# Sheet2.net
KiCad netlist of a schematic drawn in Altium Designer
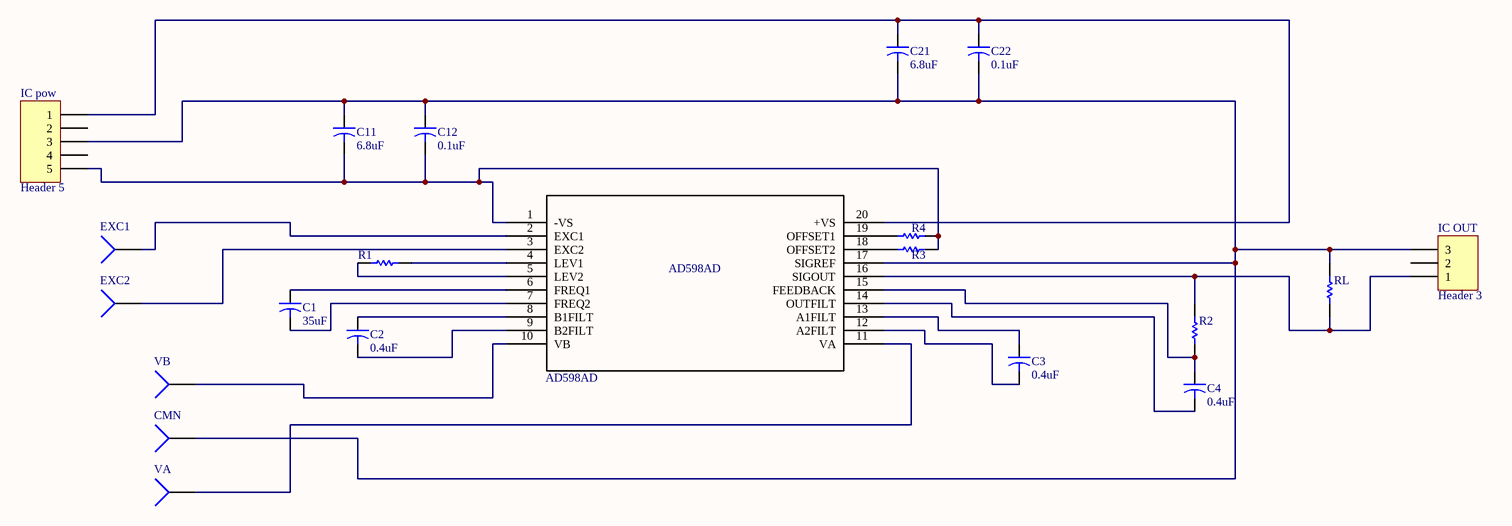
[diagram p0: Sheet2.SchDoc]

(export (version "E")
  (design (tool "Eeschema 10.0.6"))
  (components
    (comp (ref "AD598AD")
      (value "AD598AD")
      (footprint "D_20")
      (description "Imported")
      (libsource (lib "2014-03-15_12-02-51") (part "AD598AD"))
    )
    (comp (ref "C1")
      (value "35uF")
      (footprint "CAPR5-4X5")
      (description "Capacitor")
      (fields (field (name "Comment") "Cap2") (field (name "PUBLISHER") "Altium Limited"))
      (libsource (lib "Miscellaneous Devices") (part "Cap2"))
    )
    (comp (ref "C2")
      (value "0.4uF")
      (footprint "CAPR5-4X5")
      (description "Capacitor")
      (fields (field (name "Comment") "Cap2") (field (name "PUBLISHER") "Altium Limited"))
      (libsource (lib "Miscellaneous Devices") (part "Cap2"))
    )
    (comp (ref "C3")
      (value "0.4uF")
      (footprint "CAPR5-4X5")
      (description "Capacitor")
      (fields (field (name "Comment") "Cap2") (field (name "PUBLISHER") "Altium Limited"))
      (libsource (lib "Miscellaneous Devices") (part "Cap2"))
    )
    (comp (ref "C4")
      (value "0.4uF")
      (footprint "CAPR5-4X5")
      (description "Capacitor")
      (fields (field (name "Comment") "Cap2") (field (name "PUBLISHER") "Altium Limited"))
      (libsource (lib "Miscellaneous Devices") (part "Cap2"))
    )
    (comp (ref "C11")
      (value "6.8uF")
      (footprint "CAPR5-4X5")
      (description "Capacitor")
      (fields (field (name "Comment") "Cap2") (field (name "PUBLISHER") "Altium Limited"))
      (libsource (lib "Miscellaneous Devices") (part "Cap2"))
    )
    (comp (ref "C12")
      (value "0.1uF")
      (footprint "CAPR5-4X5")
      (description "Capacitor")
      (fields (field (name "Comment") "Cap2") (field (name "PUBLISHER") "Altium Limited"))
      (libsource (lib "Miscellaneous Devices") (part "Cap2"))
    )
    (comp (ref "C21")
      (value "6.8uF")
      (footprint "CAPR5-4X5")
      (description "Capacitor")
      (fields (field (name "Comment") "Cap2") (field (name "PUBLISHER") "Altium Limited"))
      (libsource (lib "Miscellaneous Devices") (part "Cap2"))
    )
    (comp (ref "C22")
      (value "0.1uF")
      (footprint "CAPR5-4X5")
      (description "Capacitor")
      (fields (field (name "Comment") "Cap2") (field (name "PUBLISHER") "Altium Limited"))
      (libsource (lib "Miscellaneous Devices") (part "Cap2"))
    )
    (comp (ref "CMN")
      (value "Socket")
      (footprint "PIN1")
      (fields (field (name "PUBLISHER") "Altium Limited"))
      (libsource (lib "Miscellaneous Connectors") (part "Socket"))
    )
    (comp (ref "EXC1")
      (value "Socket")
      (footprint "PIN1")
      (fields (field (name "PUBLISHER") "Altium Limited"))
      (libsource (lib "Miscellaneous Connectors") (part "Socket"))
    )
    (comp (ref "EXC2")
      (value "Socket")
      (footprint "PIN1")
      (fields (field (name "PUBLISHER") "Altium Limited"))
      (libsource (lib "Miscellaneous Connectors") (part "Socket"))
    )
    (comp (ref "IC OUT")
      (value "Header 3")
      (footprint "HDR1X3")
      (description "Header, 3-Pin")
      (fields (field (name "PUBLISHER") "Altium Limited"))
      (libsource (lib "Miscellaneous Connectors") (part "Header 3"))
    )
    (comp (ref "IC pow")
      (value "Header 5")
      (footprint "HDR1X5")
      (description "Header, 5-Pin")
      (fields (field (name "PUBLISHER") "Altium Limited"))
      (libsource (lib "Miscellaneous Connectors") (part "Header 5"))
    )
    (comp (ref "R1")
      (value "R1")
      (footprint "AXIAL-0.3")
      (description "Resistor")
      (fields (field (name "PUBLISHER") "Altium Limited"))
      (libsource (lib "Miscellaneous Devices") (part "Res1"))
    )
    (comp (ref "R2")
      (value "Res1")
      (footprint "AXIAL-0.3")
      (description "Resistor")
      (fields (field (name "PUBLISHER") "Altium Limited"))
      (libsource (lib "Miscellaneous Devices") (part "Res1"))
    )
    (comp (ref "R3")
      (value "Res1")
      (footprint "AXIAL-0.3")
      (description "Resistor")
      (fields (field (name "PUBLISHER") "Altium Limited"))
      (libsource (lib "Miscellaneous Devices") (part "Res1"))
    )
    (comp (ref "R4")
      (value "Res1")
      (footprint "AXIAL-0.3")
      (description "Resistor")
      (fields (field (name "PUBLISHER") "Altium Limited"))
      (libsource (lib "Miscellaneous Devices") (part "Res1"))
    )
    (comp (ref "RL")
      (value "Res1")
      (footprint "AXIAL-0.3")
      (description "Resistor")
      (fields (field (name "PUBLISHER") "Altium Limited"))
      (libsource (lib "Miscellaneous Devices") (part "Res1"))
    )
    (comp (ref "VA")
      (value "Socket")
      (footprint "PIN1")
      (fields (field (name "PUBLISHER") "Altium Limited"))
      (libsource (lib "Miscellaneous Connectors") (part "Socket"))
    )
    (comp (ref "VB")
      (value "Socket")
      (footprint "PIN1")
      (fields (field (name "PUBLISHER") "Altium Limited"))
      (libsource (lib "Miscellaneous Connectors") (part "Socket"))
    )
  )
  (nets
    (net (code "1") (name "Net-(AD598AD-+VS)") (class "Default")
      (node (ref "AD598AD") (pin "20") (pinfunction "+VS_20") (pintype "passive"))
      (node (ref "C21") (pin "1") (pinfunction "1_1") (pintype "passive"))
      (node (ref "C22") (pin "1") (pinfunction "1_1") (pintype "passive"))
      (node (ref "IC pow") (pin "1") (pinfunction "1_1") (pintype "passive"))
    )
    (net (code "2") (name "Net-(AD598AD--VS)") (class "Default")
      (node (ref "AD598AD") (pin "1") (pinfunction "-VS_1") (pintype "passive"))
      (node (ref "C11") (pin "2") (pinfunction "2_2") (pintype "passive"))
      (node (ref "C12") (pin "2") (pinfunction "2_2") (pintype "passive"))
      (node (ref "IC pow") (pin "5") (pinfunction "5_5") (pintype "passive"))
      (node (ref "R3") (pin "2") (pinfunction "2_2") (pintype "passive"))
      (node (ref "R4") (pin "2") (pinfunction "2_2") (pintype "passive"))
    )
    (net (code "3") (name "Net-(AD598AD-A1FILT)") (class "Default")
      (node (ref "AD598AD") (pin "13") (pinfunction "A1FILT_13") (pintype "passive"))
      (node (ref "C3") (pin "1") (pinfunction "1_1") (pintype "passive"))
    )
    (net (code "4") (name "Net-(AD598AD-A2FILT)") (class "Default")
      (node (ref "AD598AD") (pin "12") (pinfunction "A2FILT_12") (pintype "passive"))
      (node (ref "C3") (pin "2") (pinfunction "2_2") (pintype "passive"))
    )
    (net (code "5") (name "Net-(AD598AD-B1FILT)") (class "Default")
      (node (ref "AD598AD") (pin "8") (pinfunction "B1FILT_8") (pintype "passive"))
      (node (ref "C2") (pin "1") (pinfunction "1_1") (pintype "passive"))
    )
    (net (code "6") (name "Net-(AD598AD-B2FILT)") (class "Default")
      (node (ref "AD598AD") (pin "9") (pinfunction "B2FILT_9") (pintype "passive"))
      (node (ref "C2") (pin "2") (pinfunction "2_2") (pintype "passive"))
    )
    (net (code "7") (name "Net-(AD598AD-EXC1)") (class "Default")
      (node (ref "AD598AD") (pin "2") (pinfunction "EXC1_2") (pintype "passive"))
      (node (ref "EXC1") (pin "1") (pinfunction "1_1") (pintype "passive"))
    )
    (net (code "8") (name "Net-(AD598AD-EXC2)") (class "Default")
      (node (ref "AD598AD") (pin "3") (pinfunction "EXC2_3") (pintype "passive"))
      (node (ref "EXC2") (pin "1") (pinfunction "1_1") (pintype "passive"))
    )
    (net (code "9") (name "Net-(AD598AD-FEEDBACK)") (class "Default")
      (node (ref "AD598AD") (pin "15") (pinfunction "FEEDBACK_15") (pintype "passive"))
      (node (ref "C4") (pin "1") (pinfunction "1_1") (pintype "passive"))
      (node (ref "R2") (pin "1") (pinfunction "1_1") (pintype "passive"))
    )
    (net (code "10") (name "Net-(AD598AD-FREQ1)") (class "Default")
      (node (ref "AD598AD") (pin "6") (pinfunction "FREQ1_6") (pintype "passive"))
      (node (ref "C1") (pin "1") (pinfunction "1_1") (pintype "passive"))
    )
    (net (code "11") (name "Net-(AD598AD-FREQ2)") (class "Default")
      (node (ref "AD598AD") (pin "7") (pinfunction "FREQ2_7") (pintype "passive"))
      (node (ref "C1") (pin "2") (pinfunction "2_2") (pintype "passive"))
    )
    (net (code "12") (name "Net-(AD598AD-LEV1)") (class "Default")
      (node (ref "AD598AD") (pin "4") (pinfunction "LEV1_4") (pintype "passive"))
      (node (ref "R1") (pin "1") (pinfunction "1_1") (pintype "passive"))
    )
    (net (code "13") (name "Net-(AD598AD-LEV2)") (class "Default")
      (node (ref "AD598AD") (pin "5") (pinfunction "LEV2_5") (pintype "passive"))
      (node (ref "R1") (pin "2") (pinfunction "2_2") (pintype "passive"))
    )
    (net (code "14") (name "Net-(AD598AD-OFFSET1)") (class "Default")
      (node (ref "AD598AD") (pin "19") (pinfunction "OFFSET1_19") (pintype "passive"))
      (node (ref "R4") (pin "1") (pinfunction "1_1") (pintype "passive"))
    )
    (net (code "15") (name "Net-(AD598AD-OFFSET2)") (class "Default")
      (node (ref "AD598AD") (pin "18") (pinfunction "OFFSET2_18") (pintype "passive"))
      (node (ref "R3") (pin "1") (pinfunction "1_1") (pintype "passive"))
    )
    (net (code "16") (name "Net-(AD598AD-OUTFILT)") (class "Default")
      (node (ref "AD598AD") (pin "14") (pinfunction "OUTFILT_14") (pintype "passive"))
      (node (ref "C4") (pin "2") (pinfunction "2_2") (pintype "passive"))
    )
    (net (code "17") (name "Net-(AD598AD-SIGOUT)") (class "Default")
      (node (ref "AD598AD") (pin "16") (pinfunction "SIGOUT_16") (pintype "passive"))
      (node (ref "IC OUT") (pin "1") (pinfunction "1_1") (pintype "passive"))
      (node (ref "R2") (pin "2") (pinfunction "2_2") (pintype "passive"))
      (node (ref "RL") (pin "1") (pinfunction "1_1") (pintype "passive"))
    )
    (net (code "18") (name "Net-(AD598AD-SIGREF)") (class "Default")
      (node (ref "AD598AD") (pin "17") (pinfunction "SIGREF_17") (pintype "passive"))
      (node (ref "C11") (pin "1") (pinfunction "1_1") (pintype "passive"))
      (node (ref "C12") (pin "1") (pinfunction "1_1") (pintype "passive"))
      (node (ref "C21") (pin "2") (pinfunction "2_2") (pintype "passive"))
      (node (ref "C22") (pin "2") (pinfunction "2_2") (pintype "passive"))
      (node (ref "CMN") (pin "1") (pinfunction "1_1") (pintype "passive"))
      (node (ref "IC OUT") (pin "3") (pinfunction "3_3") (pintype "passive"))
      (node (ref "IC pow") (pin "3") (pinfunction "3_3") (pintype "passive"))
      (node (ref "RL") (pin "2") (pinfunction "2_2") (pintype "passive"))
    )
    (net (code "19") (name "Net-(AD598AD-VA)") (class "Default")
      (node (ref "AD598AD") (pin "11") (pinfunction "VA_11") (pintype "passive"))
      (node (ref "VA") (pin "1") (pinfunction "1_1") (pintype "passive"))
    )
    (net (code "20") (name "Net-(AD598AD-VB)") (class "Default")
      (node (ref "AD598AD") (pin "10") (pinfunction "VB_10") (pintype "passive"))
      (node (ref "VB") (pin "1") (pinfunction "1_1") (pintype "passive"))
    )
    (net (code "21") (name "unconnected-(IC OUT-Pad2)") (class "Default")
      (node (ref "IC OUT") (pin "2") (pinfunction "2_2") (pintype "passive"))
    )
    (net (code "22") (name "unconnected-(IC pow-Pad2)") (class "Default")
      (node (ref "IC pow") (pin "2") (pinfunction "2_2") (pintype "passive"))
    )
    (net (code "23") (name "unconnected-(IC pow-Pad4)") (class "Default")
      (node (ref "IC pow") (pin "4") (pinfunction "4_4") (pintype "passive"))
    )
  )
)
